# Arachnode.net
KiCad netlist of a schematic drawn in EAGLE
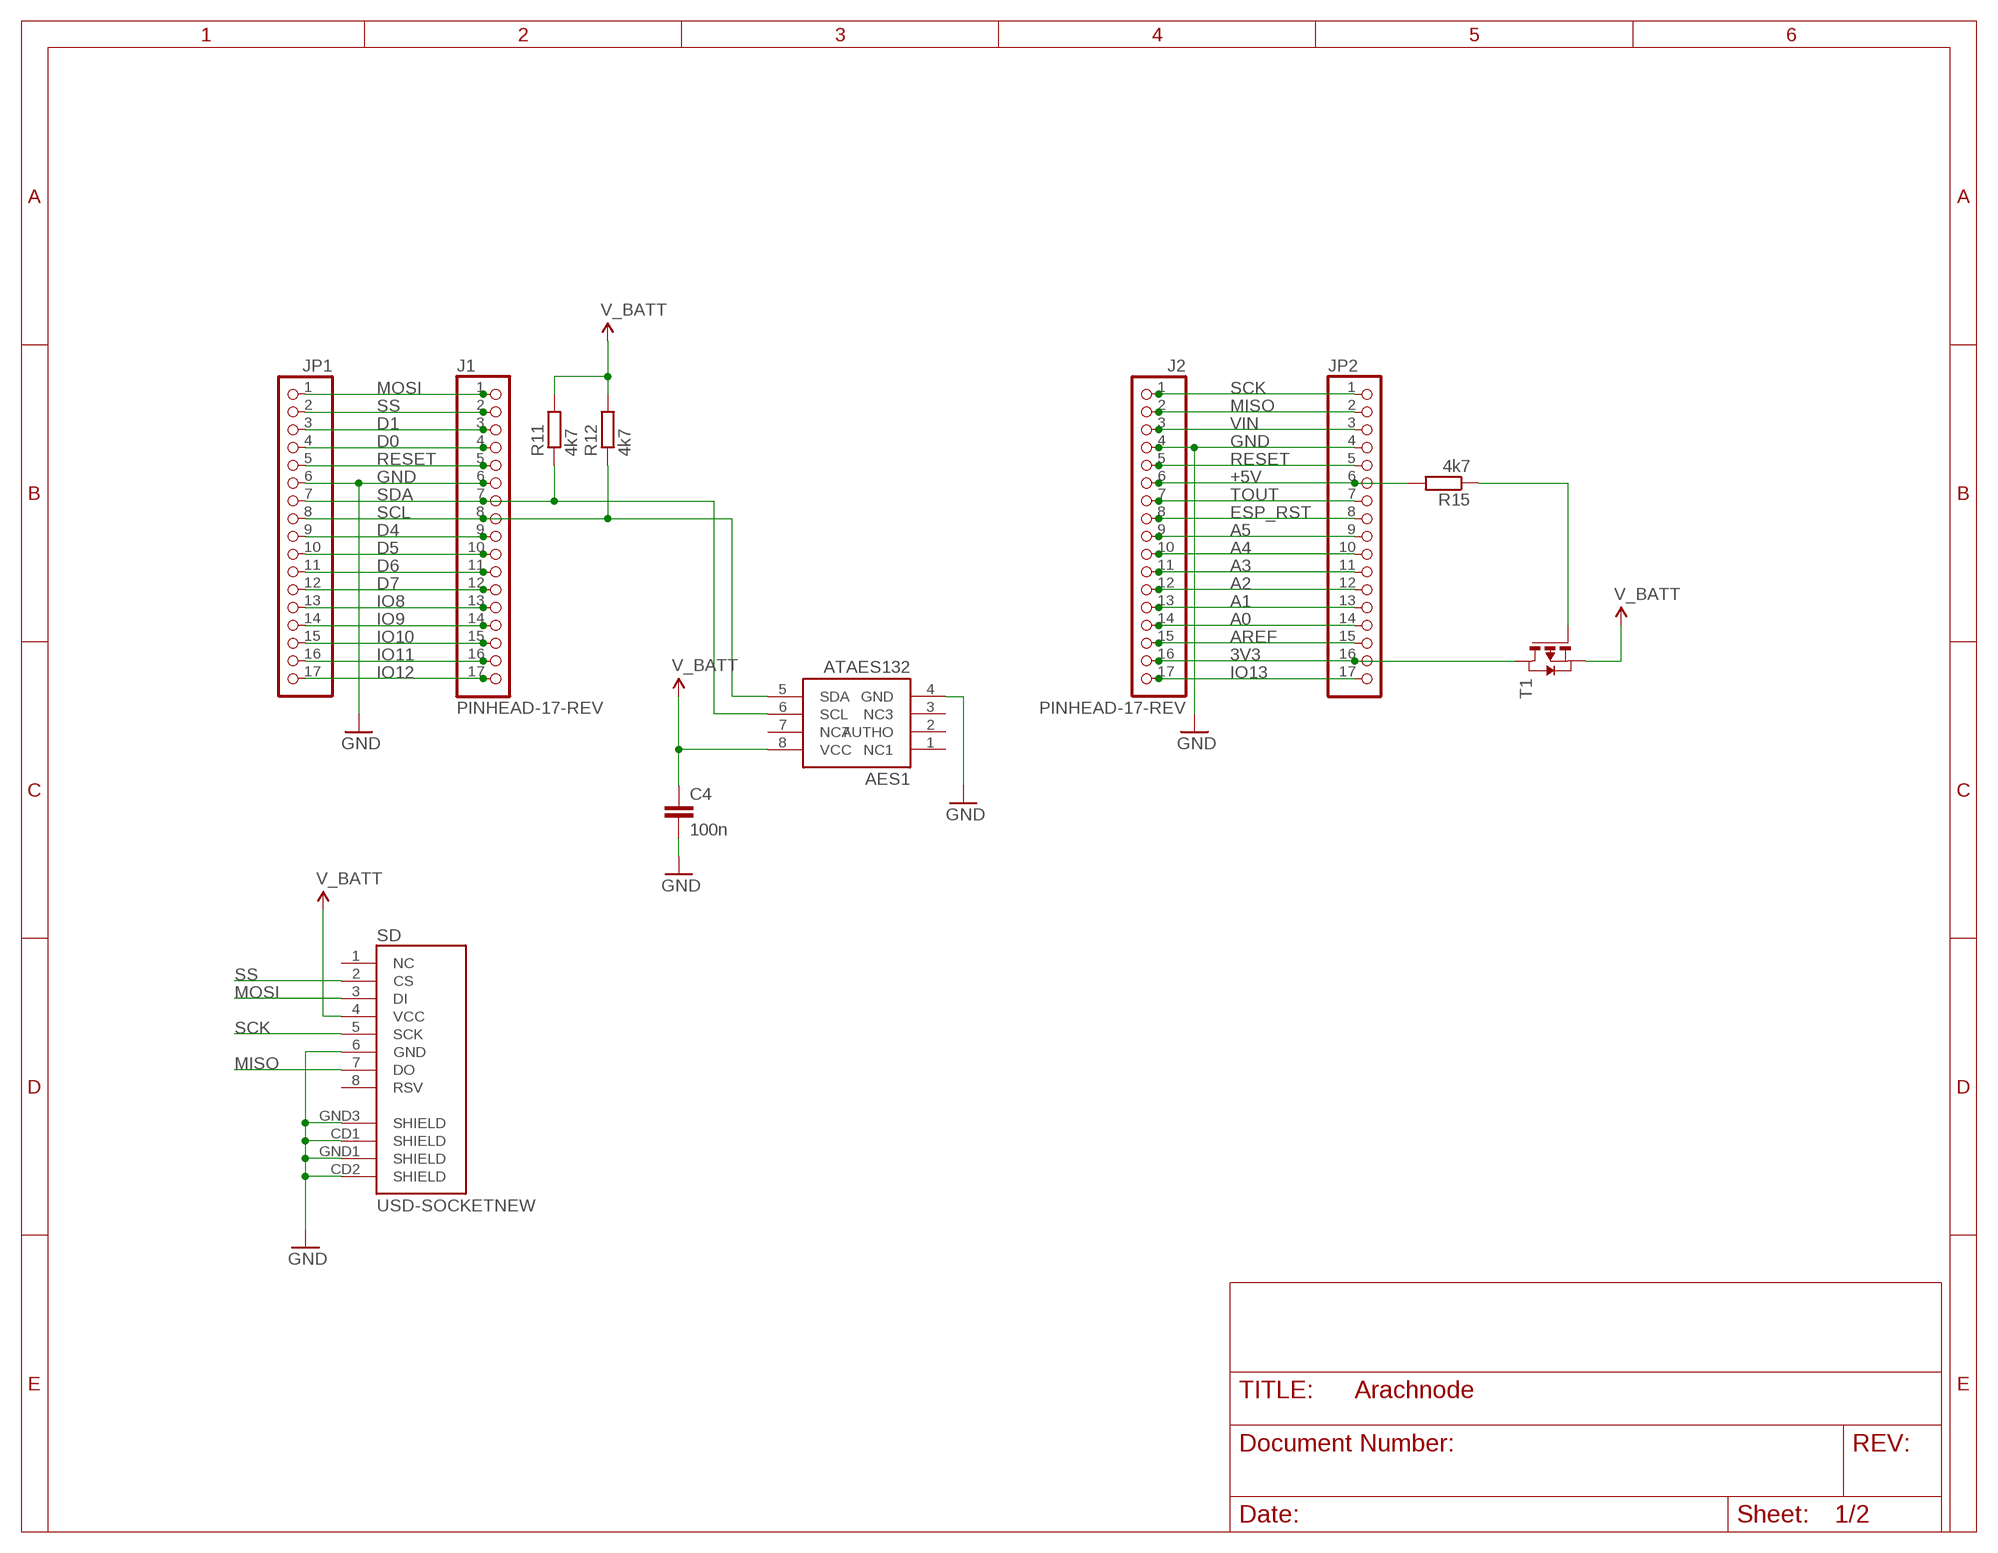
[diagram p0: schematic, sheet 1]
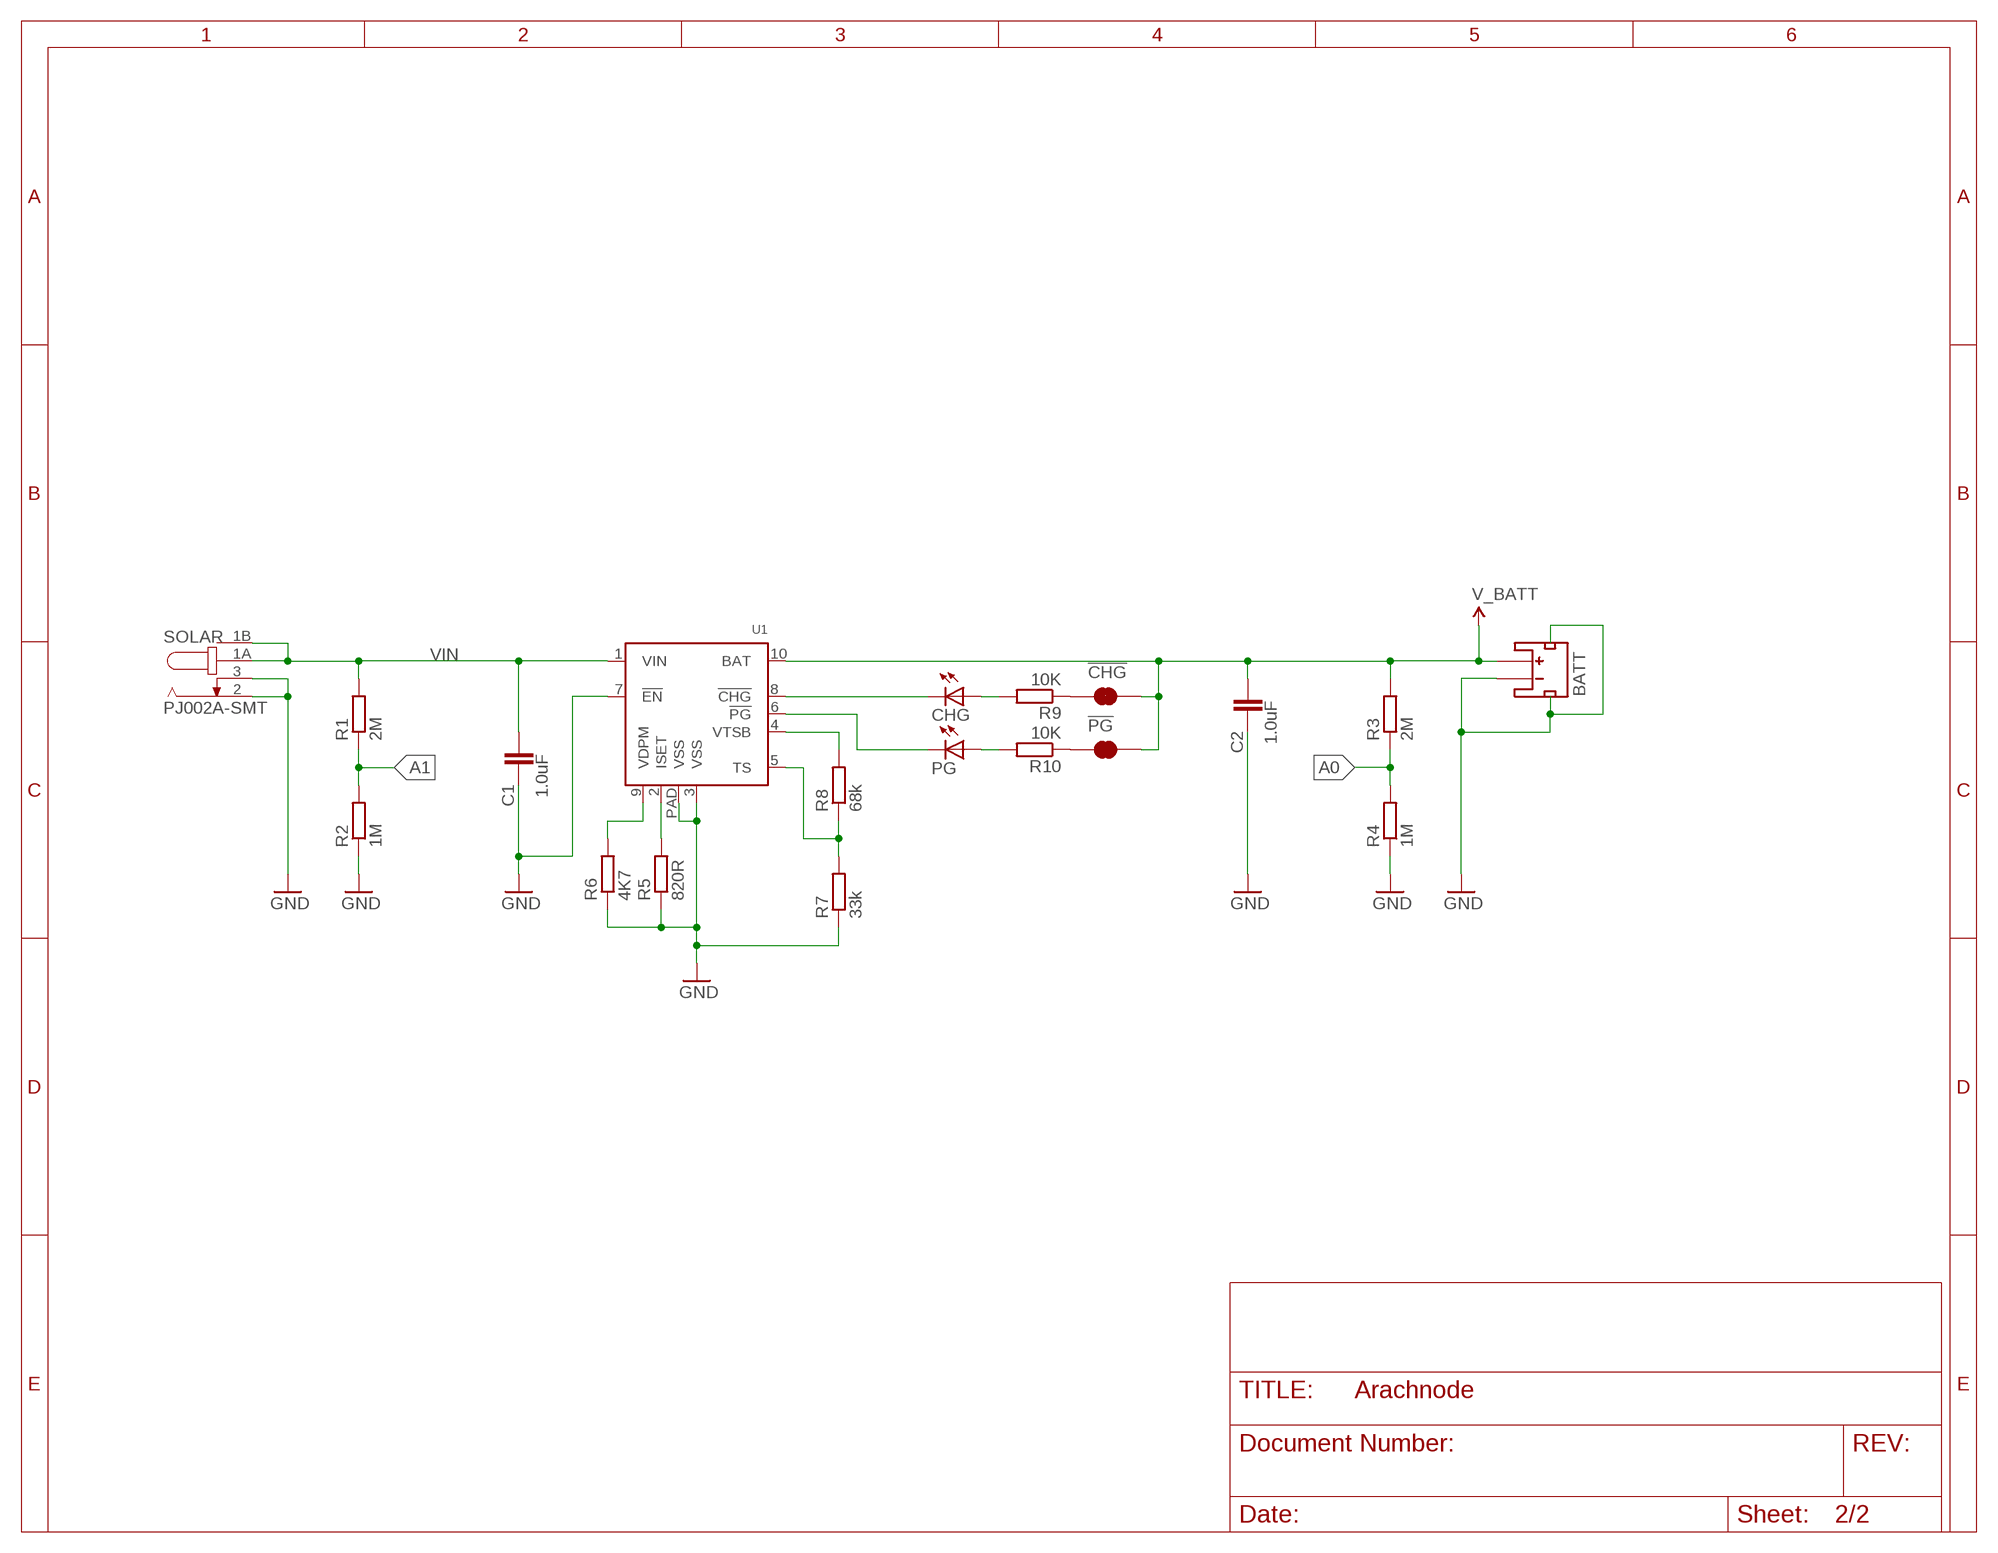
[diagram p1: schematic, sheet 2]

(export (version "E")
  (design (tool "Eeschema 10.0.6"))
  (components
    (comp (ref "AES1")
      (value "ATAES132")
      (footprint "eagle-import:SOIC8")
      (libsource (lib "eagle-import") (part "ATAES132"))
    )
    (comp (ref "C4")
      (value "100n")
      (footprint "eagle-import:C0603")
      (libsource (lib "eagle-import") (part "C-EUC0603"))
    )
    (comp (ref "J1")
      (value "PINHEAD-17-REV")
      (footprint "eagle-import:4UCONN-12573")
      (libsource (lib "eagle-import") (part "PINHEAD-17-REV"))
    )
    (comp (ref "J2")
      (value "PINHEAD-17-REV")
      (footprint "eagle-import:4UCONN-12573")
      (libsource (lib "eagle-import") (part "PINHEAD-17-REV"))
    )
    (comp (ref "JP1")
      (value "PINHD-1X17_2.54")
      (footprint "eagle-import:1X17")
      (libsource (lib "eagle-import") (part "PINHD-1X17_2.54"))
    )
    (comp (ref "JP2")
      (value "PINHD-1X17_2.54")
      (footprint "eagle-import:1X17")
      (libsource (lib "eagle-import") (part "PINHD-1X17_2.54"))
    )
    (comp (ref "R11")
      (value "4k7")
      (footprint "eagle-import:R0603")
      (libsource (lib "eagle-import") (part "R-EU_R0603"))
    )
    (comp (ref "R12")
      (value "4k7")
      (footprint "eagle-import:R0603")
      (libsource (lib "eagle-import") (part "R-EU_R0603"))
    )
    (comp (ref "R15")
      (value "4k7")
      (footprint "eagle-import:R0603")
      (libsource (lib "eagle-import") (part "R-EU_R0603"))
    )
    (comp (ref "SD")
      (value "USD-SOCKETNEW")
      (footprint "eagle-import:MICRO-SD-SOCKET-PP")
      (fields (field (name "PARTNO") "502570-0893"))
      (libsource (lib "eagle-import") (part "USD-SOCKETNEW"))
    )
    (comp (ref "T1")
      (value "PMOSSOT23")
      (footprint "eagle-import:SOT-23")
      (libsource (lib "eagle-import") (part "PMOSSOT23"))
    )
    (comp (ref "!CHG!")
      (value "JUMPER-PAD-2-NC_BY_TRACE")
      (footprint "eagle-import:PAD-JUMPER-2-NC_BY_TRACE_YES_SILK")
      (libsource (lib "eagle-import") (part "JUMPER-PAD-2-NC_BY_TRACE"))
    )
    (comp (ref "!PG!")
      (value "JUMPER-PAD-2-NC_BY_TRACE")
      (footprint "eagle-import:PAD-JUMPER-2-NC_BY_TRACE_YES_SILK")
      (libsource (lib "eagle-import") (part "JUMPER-PAD-2-NC_BY_TRACE"))
    )
    (comp (ref "BATT")
      (value "JST_2MM_MALE")
      (footprint "eagle-import:JST-2-SMD")
      (fields (field (name "PARTNO") "S2B-PH-SM4-TB(LF)(SN)"))
      (libsource (lib "eagle-import") (part "JST_2MM_MALE"))
    )
    (comp (ref "C1")
      (value "1.0uF")
      (footprint "eagle-import:C0603")
      (libsource (lib "eagle-import") (part "C-EUC0603"))
    )
    (comp (ref "C2")
      (value "1.0uF")
      (footprint "eagle-import:C0603")
      (libsource (lib "eagle-import") (part "C-EUC0603"))
    )
    (comp (ref "CHG")
      (value "LEDCHIP-LED0603")
      (footprint "eagle-import:CHIP-LED0603")
      (libsource (lib "eagle-import") (part "LEDCHIP-LED0603"))
    )
    (comp (ref "PG")
      (value "LEDCHIP-LED0603")
      (footprint "eagle-import:CHIP-LED0603")
      (libsource (lib "eagle-import") (part "LEDCHIP-LED0603"))
    )
    (comp (ref "R1")
      (value "2M")
      (footprint "eagle-import:R0603")
      (libsource (lib "eagle-import") (part "R-EU_R0603"))
    )
    (comp (ref "R2")
      (value "1M")
      (footprint "eagle-import:R0603")
      (fields (field (name "PARTNO") "ERJ-3EKF1004V"))
      (libsource (lib "eagle-import") (part "R-EU_R0603"))
    )
    (comp (ref "R3")
      (value "2M")
      (footprint "eagle-import:R0603")
      (libsource (lib "eagle-import") (part "R-EU_R0603"))
    )
    (comp (ref "R4")
      (value "1M")
      (footprint "eagle-import:R0603")
      (fields (field (name "PARTNO") "ERJ-3EKF1004V"))
      (libsource (lib "eagle-import") (part "R-EU_R0603"))
    )
    (comp (ref "R5")
      (value "820R")
      (footprint "eagle-import:R0603")
      (libsource (lib "eagle-import") (part "R-EU_R0603"))
    )
    (comp (ref "R6")
      (value "4K7")
      (footprint "eagle-import:R0603")
      (libsource (lib "eagle-import") (part "R-EU_R0603"))
    )
    (comp (ref "R7")
      (value "33k")
      (footprint "eagle-import:R0603")
      (libsource (lib "eagle-import") (part "R-EU_R0603"))
    )
    (comp (ref "R8")
      (value "68k")
      (footprint "eagle-import:R0603")
      (libsource (lib "eagle-import") (part "R-EU_R0603"))
    )
    (comp (ref "R9")
      (value "10K")
      (footprint "eagle-import:R0603")
      (libsource (lib "eagle-import") (part "R-EU_R0603"))
    )
    (comp (ref "R10")
      (value "10K")
      (footprint "eagle-import:R0603")
      (libsource (lib "eagle-import") (part "R-EU_R0603"))
    )
    (comp (ref "SOLAR")
      (value "PJ002A-SMT")
      (footprint "eagle-import:PJ002A-SMT")
      (fields (field (name "PARTNO") "PJ-002AH-SMT"))
      (libsource (lib "eagle-import") (part "PJ002A-SMT"))
    )
    (comp (ref "U1")
      (value "BQ24210")
      (footprint "eagle-import:WSON-10")
      (libsource (lib "eagle-import") (part "BQ24210"))
    )
  )
  (nets
    (net (code "1") (name "+5V") (class "Default")
      (node (ref "J2") (pin "23") (pinfunction "23_23") (pintype "passive"))
      (node (ref "J2") (pin "40") (pinfunction "40_40") (pintype "passive"))
      (node (ref "J2") (pin "6") (pinfunction "6_6") (pintype "passive"))
      (node (ref "JP2") (pin "6") (pinfunction "6_6") (pintype "passive"))
      (node (ref "R15") (pin "2") (pinfunction "2_2") (pintype "passive"))
    )
    (net (code "2") (name "3V3") (class "Default")
      (node (ref "J2") (pin "16") (pinfunction "16_16") (pintype "passive"))
      (node (ref "J2") (pin "33") (pinfunction "33_33") (pintype "passive"))
      (node (ref "J2") (pin "50") (pinfunction "50_50") (pintype "passive"))
      (node (ref "JP2") (pin "16") (pinfunction "16_16") (pintype "passive"))
      (node (ref "T1") (pin "1") (pinfunction "D_1") (pintype "passive"))
    )
    (net (code "3") (name "A0") (class "Default")
      (node (ref "J2") (pin "14") (pinfunction "14_14") (pintype "passive"))
      (node (ref "J2") (pin "31") (pinfunction "31_31") (pintype "passive"))
      (node (ref "J2") (pin "48") (pinfunction "48_48") (pintype "passive"))
      (node (ref "JP2") (pin "14") (pinfunction "14_14") (pintype "passive"))
      (node (ref "R3") (pin "1") (pinfunction "1_1") (pintype "passive"))
      (node (ref "R4") (pin "2") (pinfunction "2_2") (pintype "passive"))
    )
    (net (code "4") (name "A1") (class "Default")
      (node (ref "J2") (pin "13") (pinfunction "13_13") (pintype "passive"))
      (node (ref "J2") (pin "30") (pinfunction "30_30") (pintype "passive"))
      (node (ref "J2") (pin "47") (pinfunction "47_47") (pintype "passive"))
      (node (ref "JP2") (pin "13") (pinfunction "13_13") (pintype "passive"))
      (node (ref "R1") (pin "1") (pinfunction "1_1") (pintype "passive"))
      (node (ref "R2") (pin "2") (pinfunction "2_2") (pintype "passive"))
    )
    (net (code "5") (name "A2") (class "Default")
      (node (ref "J2") (pin "12") (pinfunction "12_12") (pintype "passive"))
      (node (ref "J2") (pin "29") (pinfunction "29_29") (pintype "passive"))
      (node (ref "J2") (pin "46") (pinfunction "46_46") (pintype "passive"))
      (node (ref "JP2") (pin "12") (pinfunction "12_12") (pintype "passive"))
    )
    (net (code "6") (name "A3") (class "Default")
      (node (ref "J2") (pin "11") (pinfunction "11_11") (pintype "passive"))
      (node (ref "J2") (pin "28") (pinfunction "28_28") (pintype "passive"))
      (node (ref "J2") (pin "45") (pinfunction "45_45") (pintype "passive"))
      (node (ref "JP2") (pin "11") (pinfunction "11_11") (pintype "passive"))
    )
    (net (code "7") (name "A4") (class "Default")
      (node (ref "J2") (pin "10") (pinfunction "10_10") (pintype "passive"))
      (node (ref "J2") (pin "27") (pinfunction "27_27") (pintype "passive"))
      (node (ref "J2") (pin "44") (pinfunction "44_44") (pintype "passive"))
      (node (ref "JP2") (pin "10") (pinfunction "10_10") (pintype "passive"))
    )
    (net (code "8") (name "A5") (class "Default")
      (node (ref "J2") (pin "26") (pinfunction "26_26") (pintype "passive"))
      (node (ref "J2") (pin "43") (pinfunction "43_43") (pintype "passive"))
      (node (ref "J2") (pin "9") (pinfunction "9_9") (pintype "passive"))
      (node (ref "JP2") (pin "9") (pinfunction "9_9") (pintype "passive"))
    )
    (net (code "9") (name "AREF") (class "Default")
      (node (ref "J2") (pin "15") (pinfunction "15_15") (pintype "passive"))
      (node (ref "J2") (pin "32") (pinfunction "32_32") (pintype "passive"))
      (node (ref "J2") (pin "49") (pinfunction "49_49") (pintype "passive"))
      (node (ref "JP2") (pin "15") (pinfunction "15_15") (pintype "passive"))
    )
    (net (code "10") (name "D0") (class "Default")
      (node (ref "J1") (pin "21") (pinfunction "21_21") (pintype "passive"))
      (node (ref "J1") (pin "38") (pinfunction "38_38") (pintype "passive"))
      (node (ref "J1") (pin "4") (pinfunction "4_4") (pintype "passive"))
      (node (ref "JP1") (pin "4") (pinfunction "4_4") (pintype "passive"))
    )
    (net (code "11") (name "D1") (class "Default")
      (node (ref "J1") (pin "20") (pinfunction "20_20") (pintype "passive"))
      (node (ref "J1") (pin "3") (pinfunction "3_3") (pintype "passive"))
      (node (ref "J1") (pin "37") (pinfunction "37_37") (pintype "passive"))
      (node (ref "JP1") (pin "3") (pinfunction "3_3") (pintype "passive"))
    )
    (net (code "12") (name "D4") (class "Default")
      (node (ref "J1") (pin "26") (pinfunction "26_26") (pintype "passive"))
      (node (ref "J1") (pin "43") (pinfunction "43_43") (pintype "passive"))
      (node (ref "J1") (pin "9") (pinfunction "9_9") (pintype "passive"))
      (node (ref "JP1") (pin "9") (pinfunction "9_9") (pintype "passive"))
    )
    (net (code "13") (name "D5") (class "Default")
      (node (ref "J1") (pin "10") (pinfunction "10_10") (pintype "passive"))
      (node (ref "J1") (pin "27") (pinfunction "27_27") (pintype "passive"))
      (node (ref "J1") (pin "44") (pinfunction "44_44") (pintype "passive"))
      (node (ref "JP1") (pin "10") (pinfunction "10_10") (pintype "passive"))
    )
    (net (code "14") (name "D6") (class "Default")
      (node (ref "J1") (pin "11") (pinfunction "11_11") (pintype "passive"))
      (node (ref "J1") (pin "28") (pinfunction "28_28") (pintype "passive"))
      (node (ref "J1") (pin "45") (pinfunction "45_45") (pintype "passive"))
      (node (ref "JP1") (pin "11") (pinfunction "11_11") (pintype "passive"))
    )
    (net (code "15") (name "D7") (class "Default")
      (node (ref "J1") (pin "12") (pinfunction "12_12") (pintype "passive"))
      (node (ref "J1") (pin "29") (pinfunction "29_29") (pintype "passive"))
      (node (ref "J1") (pin "46") (pinfunction "46_46") (pintype "passive"))
      (node (ref "JP1") (pin "12") (pinfunction "12_12") (pintype "passive"))
    )
    (net (code "16") (name "ESP_RST") (class "Default")
      (node (ref "J2") (pin "25") (pinfunction "25_25") (pintype "passive"))
      (node (ref "J2") (pin "42") (pinfunction "42_42") (pintype "passive"))
      (node (ref "J2") (pin "8") (pinfunction "8_8") (pintype "passive"))
      (node (ref "JP2") (pin "8") (pinfunction "8_8") (pintype "passive"))
    )
    (net (code "17") (name "GND") (class "Default")
      (node (ref "AES1") (pin "4") (pinfunction "GND_4") (pintype "power_in"))
      (node (ref "BATT") (pin "1") (pinfunction "-_1") (pintype "bidirectional"))
      (node (ref "BATT") (pin "NC1") (pinfunction "PAD1_NC1") (pintype "bidirectional"))
      (node (ref "BATT") (pin "NC2") (pinfunction "PAD2_NC2") (pintype "bidirectional"))
      (node (ref "C1") (pin "1") (pinfunction "1_1") (pintype "passive"))
      (node (ref "C2") (pin "1") (pinfunction "1_1") (pintype "passive"))
      (node (ref "C4") (pin "2") (pinfunction "2_2") (pintype "passive"))
      (node (ref "J1") (pin "23") (pinfunction "23_23") (pintype "passive"))
      (node (ref "J1") (pin "40") (pinfunction "40_40") (pintype "passive"))
      (node (ref "J1") (pin "6") (pinfunction "6_6") (pintype "passive"))
      (node (ref "J2") (pin "21") (pinfunction "21_21") (pintype "passive"))
      (node (ref "J2") (pin "38") (pinfunction "38_38") (pintype "passive"))
      (node (ref "J2") (pin "4") (pinfunction "4_4") (pintype "passive"))
      (node (ref "JP1") (pin "6") (pinfunction "6_6") (pintype "passive"))
      (node (ref "JP2") (pin "4") (pinfunction "4_4") (pintype "passive"))
      (node (ref "R2") (pin "1") (pinfunction "1_1") (pintype "passive"))
      (node (ref "R4") (pin "1") (pinfunction "1_1") (pintype "passive"))
      (node (ref "R5") (pin "1") (pinfunction "1_1") (pintype "passive"))
      (node (ref "R6") (pin "1") (pinfunction "1_1") (pintype "passive"))
      (node (ref "R7") (pin "1") (pinfunction "1_1") (pintype "passive"))
      (node (ref "SD") (pin "6") (pinfunction "GND_6") (pintype "bidirectional"))
      (node (ref "SD") (pin "CD1") (pinfunction "SHIELD_CD1") (pintype "bidirectional"))
      (node (ref "SD") (pin "CD2") (pinfunction "SHIELD_CD2") (pintype "bidirectional"))
      (node (ref "SD") (pin "GND1") (pinfunction "SHIELD_GND1") (pintype "bidirectional"))
      (node (ref "SD") (pin "GND3") (pinfunction "SHIELD_GND3") (pintype "bidirectional"))
      (node (ref "SOLAR") (pin "2") (pinfunction "2_2") (pintype "passive"))
      (node (ref "SOLAR") (pin "3") (pinfunction "3_3") (pintype "passive"))
      (node (ref "U1") (pin "3") (pinfunction "VSS_3") (pintype "bidirectional"))
      (node (ref "U1") (pin "7") (pinfunction "~{EN}_7") (pintype "bidirectional"))
      (node (ref "U1") (pin "PAD") (pinfunction "VSS_PAD") (pintype "bidirectional"))
    )
    (net (code "18") (name "IO8") (class "Default")
      (node (ref "J1") (pin "13") (pinfunction "13_13") (pintype "passive"))
      (node (ref "J1") (pin "30") (pinfunction "30_30") (pintype "passive"))
      (node (ref "J1") (pin "47") (pinfunction "47_47") (pintype "passive"))
      (node (ref "JP1") (pin "13") (pinfunction "13_13") (pintype "passive"))
    )
    (net (code "19") (name "IO9") (class "Default")
      (node (ref "J1") (pin "14") (pinfunction "14_14") (pintype "passive"))
      (node (ref "J1") (pin "31") (pinfunction "31_31") (pintype "passive"))
      (node (ref "J1") (pin "48") (pinfunction "48_48") (pintype "passive"))
      (node (ref "JP1") (pin "14") (pinfunction "14_14") (pintype "passive"))
    )
    (net (code "20") (name "IO10") (class "Default")
      (node (ref "J1") (pin "15") (pinfunction "15_15") (pintype "passive"))
      (node (ref "J1") (pin "32") (pinfunction "32_32") (pintype "passive"))
      (node (ref "J1") (pin "49") (pinfunction "49_49") (pintype "passive"))
      (node (ref "JP1") (pin "15") (pinfunction "15_15") (pintype "passive"))
    )
    (net (code "21") (name "IO11") (class "Default")
      (node (ref "J1") (pin "16") (pinfunction "16_16") (pintype "passive"))
      (node (ref "J1") (pin "33") (pinfunction "33_33") (pintype "passive"))
      (node (ref "J1") (pin "50") (pinfunction "50_50") (pintype "passive"))
      (node (ref "JP1") (pin "16") (pinfunction "16_16") (pintype "passive"))
    )
    (net (code "22") (name "IO12") (class "Default")
      (node (ref "J1") (pin "17") (pinfunction "17_17") (pintype "passive"))
      (node (ref "J1") (pin "34") (pinfunction "34_34") (pintype "passive"))
      (node (ref "J1") (pin "51") (pinfunction "51_51") (pintype "passive"))
      (node (ref "JP1") (pin "17") (pinfunction "17_17") (pintype "passive"))
    )
    (net (code "23") (name "IO13") (class "Default")
      (node (ref "J2") (pin "17") (pinfunction "17_17") (pintype "passive"))
      (node (ref "J2") (pin "34") (pinfunction "34_34") (pintype "passive"))
      (node (ref "J2") (pin "51") (pinfunction "51_51") (pintype "passive"))
      (node (ref "JP2") (pin "17") (pinfunction "17_17") (pintype "passive"))
    )
    (net (code "24") (name "MISO") (class "Default")
      (node (ref "J2") (pin "19") (pinfunction "19_19") (pintype "passive"))
      (node (ref "J2") (pin "2") (pinfunction "2_2") (pintype "passive"))
      (node (ref "J2") (pin "36") (pinfunction "36_36") (pintype "passive"))
      (node (ref "JP2") (pin "2") (pinfunction "2_2") (pintype "passive"))
      (node (ref "SD") (pin "7") (pinfunction "DO_7") (pintype "bidirectional"))
    )
    (net (code "25") (name "MOSI") (class "Default")
      (node (ref "J1") (pin "1") (pinfunction "1_1") (pintype "passive"))
      (node (ref "J1") (pin "18") (pinfunction "18_18") (pintype "passive"))
      (node (ref "J1") (pin "35") (pinfunction "35_35") (pintype "passive"))
      (node (ref "JP1") (pin "1") (pinfunction "1_1") (pintype "passive"))
      (node (ref "SD") (pin "3") (pinfunction "DI_3") (pintype "bidirectional"))
    )
    (net (code "26") (name "Net-(!CHG!-Pad1)") (class "Default")
      (node (ref "!CHG!") (pin "1") (pinfunction "1_1") (pintype "passive"))
      (node (ref "R9") (pin "1") (pinfunction "1_1") (pintype "passive"))
    )
    (net (code "27") (name "Net-(!PG!-Pad1)") (class "Default")
      (node (ref "!PG!") (pin "1") (pinfunction "1_1") (pintype "passive"))
      (node (ref "R10") (pin "1") (pinfunction "1_1") (pintype "passive"))
    )
    (net (code "28") (name "Net-(CHG-PadA)") (class "Default")
      (node (ref "CHG") (pin "A") (pinfunction "A_A") (pintype "passive"))
      (node (ref "R9") (pin "2") (pinfunction "2_2") (pintype "passive"))
    )
    (net (code "29") (name "Net-(PG-PadA)") (class "Default")
      (node (ref "PG") (pin "A") (pinfunction "A_A") (pintype "passive"))
      (node (ref "R10") (pin "2") (pinfunction "2_2") (pintype "passive"))
    )
    (net (code "30") (name "Net-(T1-G)") (class "Default")
      (node (ref "R15") (pin "1") (pinfunction "1_1") (pintype "passive"))
      (node (ref "T1") (pin "3") (pinfunction "G_3") (pintype "passive"))
    )
    (net (code "31") (name "Net-(U1-ISET)") (class "Default")
      (node (ref "R5") (pin "2") (pinfunction "2_2") (pintype "passive"))
      (node (ref "U1") (pin "2") (pinfunction "ISET_2") (pintype "bidirectional"))
    )
    (net (code "32") (name "Net-(U1-TS)") (class "Default")
      (node (ref "R7") (pin "2") (pinfunction "2_2") (pintype "passive"))
      (node (ref "R8") (pin "1") (pinfunction "1_1") (pintype "passive"))
      (node (ref "U1") (pin "5") (pinfunction "TS_5") (pintype "bidirectional"))
    )
    (net (code "33") (name "Net-(U1-VDPM)") (class "Default")
      (node (ref "R6") (pin "2") (pinfunction "2_2") (pintype "passive"))
      (node (ref "U1") (pin "9") (pinfunction "VDPM_9") (pintype "bidirectional"))
    )
    (net (code "34") (name "Net-(U1-VTSB)") (class "Default")
      (node (ref "R8") (pin "2") (pinfunction "2_2") (pintype "passive"))
      (node (ref "U1") (pin "4") (pinfunction "VTSB_4") (pintype "bidirectional"))
    )
    (net (code "35") (name "Net-(U1-~{CHG})") (class "Default")
      (node (ref "CHG") (pin "C") (pinfunction "C_C") (pintype "passive"))
      (node (ref "U1") (pin "8") (pinfunction "~{CHG}_8") (pintype "bidirectional"))
    )
    (net (code "36") (name "Net-(U1-~{PG})") (class "Default")
      (node (ref "PG") (pin "C") (pinfunction "C_C") (pintype "passive"))
      (node (ref "U1") (pin "6") (pinfunction "~{PG}_6") (pintype "bidirectional"))
    )
    (net (code "37") (name "RESET") (class "Default")
      (node (ref "J1") (pin "22") (pinfunction "22_22") (pintype "passive"))
      (node (ref "J1") (pin "39") (pinfunction "39_39") (pintype "passive"))
      (node (ref "J1") (pin "5") (pinfunction "5_5") (pintype "passive"))
      (node (ref "J2") (pin "22") (pinfunction "22_22") (pintype "passive"))
      (node (ref "J2") (pin "39") (pinfunction "39_39") (pintype "passive"))
      (node (ref "J2") (pin "5") (pinfunction "5_5") (pintype "passive"))
      (node (ref "JP1") (pin "5") (pinfunction "5_5") (pintype "passive"))
      (node (ref "JP2") (pin "5") (pinfunction "5_5") (pintype "passive"))
    )
    (net (code "38") (name "SCK") (class "Default")
      (node (ref "J2") (pin "1") (pinfunction "1_1") (pintype "passive"))
      (node (ref "J2") (pin "18") (pinfunction "18_18") (pintype "passive"))
      (node (ref "J2") (pin "35") (pinfunction "35_35") (pintype "passive"))
      (node (ref "JP2") (pin "1") (pinfunction "1_1") (pintype "passive"))
      (node (ref "SD") (pin "5") (pinfunction "SCK_5") (pintype "bidirectional"))
    )
    (net (code "39") (name "SCL") (class "Default")
      (node (ref "AES1") (pin "5") (pinfunction "SDA_5") (pintype "bidirectional"))
      (node (ref "J1") (pin "25") (pinfunction "25_25") (pintype "passive"))
      (node (ref "J1") (pin "42") (pinfunction "42_42") (pintype "passive"))
      (node (ref "J1") (pin "8") (pinfunction "8_8") (pintype "passive"))
      (node (ref "JP1") (pin "8") (pinfunction "8_8") (pintype "passive"))
      (node (ref "R12") (pin "1") (pinfunction "1_1") (pintype "passive"))
    )
    (net (code "40") (name "SDA") (class "Default")
      (node (ref "AES1") (pin "6") (pinfunction "SCL_6") (pintype "bidirectional"))
      (node (ref "J1") (pin "24") (pinfunction "24_24") (pintype "passive"))
      (node (ref "J1") (pin "41") (pinfunction "41_41") (pintype "passive"))
      (node (ref "J1") (pin "7") (pinfunction "7_7") (pintype "passive"))
      (node (ref "JP1") (pin "7") (pinfunction "7_7") (pintype "passive"))
      (node (ref "R11") (pin "1") (pinfunction "1_1") (pintype "passive"))
    )
    (net (code "41") (name "SS") (class "Default")
      (node (ref "J1") (pin "19") (pinfunction "19_19") (pintype "passive"))
      (node (ref "J1") (pin "2") (pinfunction "2_2") (pintype "passive"))
      (node (ref "J1") (pin "36") (pinfunction "36_36") (pintype "passive"))
      (node (ref "JP1") (pin "2") (pinfunction "2_2") (pintype "passive"))
      (node (ref "SD") (pin "2") (pinfunction "CS_2") (pintype "bidirectional"))
    )
    (net (code "42") (name "TOUT") (class "Default")
      (node (ref "J2") (pin "24") (pinfunction "24_24") (pintype "passive"))
      (node (ref "J2") (pin "41") (pinfunction "41_41") (pintype "passive"))
      (node (ref "J2") (pin "7") (pinfunction "7_7") (pintype "passive"))
      (node (ref "JP2") (pin "7") (pinfunction "7_7") (pintype "passive"))
    )
    (net (code "43") (name "VIN") (class "Default")
      (node (ref "C1") (pin "2") (pinfunction "2_2") (pintype "passive"))
      (node (ref "J2") (pin "20") (pinfunction "20_20") (pintype "passive"))
      (node (ref "J2") (pin "3") (pinfunction "3_3") (pintype "passive"))
      (node (ref "J2") (pin "37") (pinfunction "37_37") (pintype "passive"))
      (node (ref "JP2") (pin "3") (pinfunction "3_3") (pintype "passive"))
      (node (ref "R1") (pin "2") (pinfunction "2_2") (pintype "passive"))
      (node (ref "SOLAR") (pin "1A") (pinfunction "1A_1A") (pintype "passive"))
      (node (ref "SOLAR") (pin "1B") (pinfunction "1B_1B") (pintype "passive"))
      (node (ref "U1") (pin "1") (pinfunction "VIN_1") (pintype "bidirectional"))
    )
    (net (code "44") (name "V_BATT") (class "Default")
      (node (ref "!CHG!") (pin "2") (pinfunction "2_2") (pintype "passive"))
      (node (ref "!PG!") (pin "2") (pinfunction "2_2") (pintype "passive"))
      (node (ref "AES1") (pin "8") (pinfunction "VCC_8") (pintype "power_in"))
      (node (ref "BATT") (pin "2") (pinfunction "+_2") (pintype "bidirectional"))
      (node (ref "C2") (pin "2") (pinfunction "2_2") (pintype "passive"))
      (node (ref "C4") (pin "1") (pinfunction "1_1") (pintype "passive"))
      (node (ref "R11") (pin "2") (pinfunction "2_2") (pintype "passive"))
      (node (ref "R12") (pin "2") (pinfunction "2_2") (pintype "passive"))
      (node (ref "R3") (pin "2") (pinfunction "2_2") (pintype "passive"))
      (node (ref "SD") (pin "4") (pinfunction "VCC_4") (pintype "bidirectional"))
      (node (ref "T1") (pin "2") (pinfunction "S_2") (pintype "passive"))
      (node (ref "U1") (pin "10") (pinfunction "BAT_10") (pintype "bidirectional"))
    )
    (net (code "45") (name "unconnected-(AES1-AUTHO-Pad2)") (class "Default")
      (node (ref "AES1") (pin "2") (pinfunction "AUTHO_2") (pintype "bidirectional"))
    )
    (net (code "46") (name "unconnected-(AES1-NC1-Pad1)") (class "Default")
      (node (ref "AES1") (pin "1") (pinfunction "NC1_1") (pintype "no_connect"))
    )
    (net (code "47") (name "unconnected-(AES1-NC3-Pad3)") (class "Default")
      (node (ref "AES1") (pin "3") (pinfunction "NC3_3") (pintype "no_connect"))
    )
    (net (code "48") (name "unconnected-(AES1-NC7-Pad7)") (class "Default")
      (node (ref "AES1") (pin "7") (pinfunction "NC7_7") (pintype "no_connect"))
    )
    (net (code "49") (name "unconnected-(SD-NC-Pad1)") (class "Default")
      (node (ref "SD") (pin "1") (pinfunction "NC_1") (pintype "bidirectional"))
    )
    (net (code "50") (name "unconnected-(SD-RSV-Pad8)") (class "Default")
      (node (ref "SD") (pin "8") (pinfunction "RSV_8") (pintype "bidirectional"))
    )
  )
)
